# KeyPad.net
KiCad netlist of a schematic drawn in EAGLE
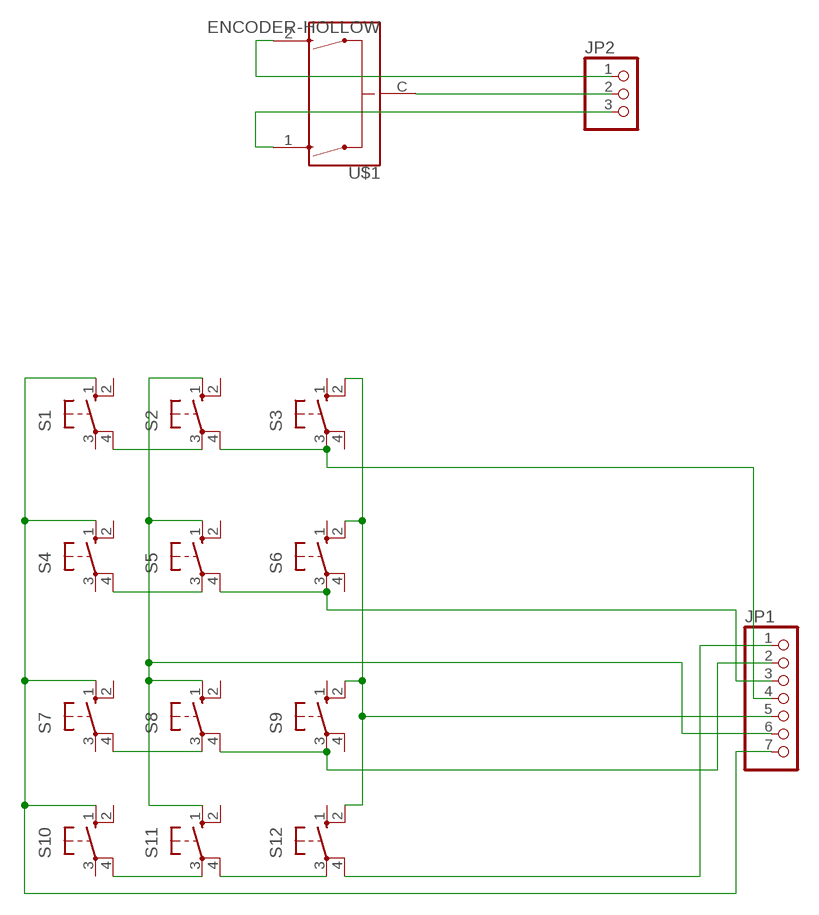
[diagram p0: schematic, sheet 1]

(export (version "E")
  (design (tool "Eeschema 10.0.6"))
  (components
    (comp (ref "JP1")
      (value "PINHD-1X7/90")
      (footprint "eagle-import:1X07_90")
      (libsource (lib "eagle-import") (part "PINHD-1X7/90"))
    )
    (comp (ref "JP2")
      (value "PINHD-1X3/90")
      (footprint "eagle-import:1X03_90")
      (libsource (lib "eagle-import") (part "PINHD-1X3/90"))
    )
    (comp (ref "S1")
      (value "40-XX")
      (footprint "eagle-import:B3F-40XX")
      (fields (field (name "MF") "OMRON COMPONENTS USA") (field (name "MPN") "B3F-4000"))
      (libsource (lib "eagle-import") (part "40-XX"))
    )
    (comp (ref "S2")
      (value "40-XX")
      (footprint "eagle-import:B3F-40XX")
      (fields (field (name "MF") "OMRON COMPONENTS USA") (field (name "MPN") "B3F-4000"))
      (libsource (lib "eagle-import") (part "40-XX"))
    )
    (comp (ref "S3")
      (value "40-XX")
      (footprint "eagle-import:B3F-40XX")
      (fields (field (name "MF") "OMRON COMPONENTS USA") (field (name "MPN") "B3F-4000"))
      (libsource (lib "eagle-import") (part "40-XX"))
    )
    (comp (ref "S4")
      (value "40-XX")
      (footprint "eagle-import:B3F-40XX")
      (fields (field (name "MF") "OMRON COMPONENTS USA") (field (name "MPN") "B3F-4000"))
      (libsource (lib "eagle-import") (part "40-XX"))
    )
    (comp (ref "S5")
      (value "40-XX")
      (footprint "eagle-import:B3F-40XX")
      (fields (field (name "MF") "OMRON COMPONENTS USA") (field (name "MPN") "B3F-4000"))
      (libsource (lib "eagle-import") (part "40-XX"))
    )
    (comp (ref "S6")
      (value "40-XX")
      (footprint "eagle-import:B3F-40XX")
      (fields (field (name "MF") "OMRON COMPONENTS USA") (field (name "MPN") "B3F-4000"))
      (libsource (lib "eagle-import") (part "40-XX"))
    )
    (comp (ref "S7")
      (value "40-XX")
      (footprint "eagle-import:B3F-40XX")
      (fields (field (name "MF") "OMRON COMPONENTS USA") (field (name "MPN") "B3F-4000"))
      (libsource (lib "eagle-import") (part "40-XX"))
    )
    (comp (ref "S8")
      (value "40-XX")
      (footprint "eagle-import:B3F-40XX")
      (fields (field (name "MF") "OMRON COMPONENTS USA") (field (name "MPN") "B3F-4000"))
      (libsource (lib "eagle-import") (part "40-XX"))
    )
    (comp (ref "S9")
      (value "40-XX")
      (footprint "eagle-import:B3F-40XX")
      (fields (field (name "MF") "OMRON COMPONENTS USA") (field (name "MPN") "B3F-4000"))
      (libsource (lib "eagle-import") (part "40-XX"))
    )
    (comp (ref "S10")
      (value "40-XX")
      (footprint "eagle-import:B3F-40XX")
      (fields (field (name "MF") "OMRON COMPONENTS USA") (field (name "MPN") "B3F-4000"))
      (libsource (lib "eagle-import") (part "40-XX"))
    )
    (comp (ref "S11")
      (value "40-XX")
      (footprint "eagle-import:B3F-40XX")
      (fields (field (name "MF") "OMRON COMPONENTS USA") (field (name "MPN") "B3F-4000"))
      (libsource (lib "eagle-import") (part "40-XX"))
    )
    (comp (ref "S12")
      (value "40-XX")
      (footprint "eagle-import:B3F-40XX")
      (fields (field (name "MF") "OMRON COMPONENTS USA") (field (name "MPN") "B3F-4000"))
      (libsource (lib "eagle-import") (part "40-XX"))
    )
    (comp (ref "U$1")
      (value "ENCODER-HOLLOW")
      (footprint "eagle-import:HOLLOW-ENCODER")
      (libsource (lib "eagle-import") (part "ENCODER-HOLLOW"))
    )
  )
  (nets
    (net (code "1") (name "Net-(JP2-Pad2)") (class "Default")
      (node (ref "JP2") (pin "2") (pinfunction "2_2") (pintype "passive"))
      (node (ref "U$1") (pin "C") (pinfunction "C_C") (pintype "bidirectional"))
    )
    (net (code "2") (name "Net-(S1-P1)") (class "Default")
      (node (ref "S1") (pin "4") (pinfunction "P1_4") (pintype "passive"))
      (node (ref "S2") (pin "3") (pinfunction "P_3") (pintype "passive"))
    )
    (net (code "3") (name "Net-(S1-S)") (class "Default")
      (node (ref "JP1") (pin "7") (pinfunction "7_7") (pintype "passive"))
      (node (ref "S1") (pin "1") (pinfunction "S_1") (pintype "passive"))
      (node (ref "S10") (pin "1") (pinfunction "S_1") (pintype "passive"))
      (node (ref "S4") (pin "1") (pinfunction "S_1") (pintype "passive"))
      (node (ref "S7") (pin "1") (pinfunction "S_1") (pintype "passive"))
    )
    (net (code "4") (name "Net-(S2-P1)") (class "Default")
      (node (ref "JP1") (pin "4") (pinfunction "4_4") (pintype "passive"))
      (node (ref "S2") (pin "4") (pinfunction "P1_4") (pintype "passive"))
      (node (ref "S3") (pin "3") (pinfunction "P_3") (pintype "passive"))
    )
    (net (code "5") (name "Net-(S4-P1)") (class "Default")
      (node (ref "S4") (pin "4") (pinfunction "P1_4") (pintype "passive"))
      (node (ref "S5") (pin "3") (pinfunction "P_3") (pintype "passive"))
    )
    (net (code "6") (name "Net-(S5-P1)") (class "Default")
      (node (ref "JP1") (pin "3") (pinfunction "3_3") (pintype "passive"))
      (node (ref "S5") (pin "4") (pinfunction "P1_4") (pintype "passive"))
      (node (ref "S6") (pin "3") (pinfunction "P_3") (pintype "passive"))
    )
    (net (code "7") (name "Net-(S7-P1)") (class "Default")
      (node (ref "S7") (pin "4") (pinfunction "P1_4") (pintype "passive"))
      (node (ref "S8") (pin "3") (pinfunction "P_3") (pintype "passive"))
    )
    (net (code "8") (name "Net-(S8-P1)") (class "Default")
      (node (ref "JP1") (pin "2") (pinfunction "2_2") (pintype "passive"))
      (node (ref "S8") (pin "4") (pinfunction "P1_4") (pintype "passive"))
      (node (ref "S9") (pin "3") (pinfunction "P_3") (pintype "passive"))
    )
    (net (code "9") (name "Net-(S10-P1)") (class "Default")
      (node (ref "S10") (pin "4") (pinfunction "P1_4") (pintype "passive"))
      (node (ref "S11") (pin "3") (pinfunction "P_3") (pintype "passive"))
    )
    (net (code "10") (name "Net-(S11-P1)") (class "Default")
      (node (ref "S11") (pin "4") (pinfunction "P1_4") (pintype "passive"))
      (node (ref "S12") (pin "3") (pinfunction "P_3") (pintype "passive"))
    )
    (net (code "11") (name "Net-(S11-S)") (class "Default")
      (node (ref "JP1") (pin "6") (pinfunction "6_6") (pintype "passive"))
      (node (ref "S11") (pin "1") (pinfunction "S_1") (pintype "passive"))
      (node (ref "S2") (pin "1") (pinfunction "S_1") (pintype "passive"))
      (node (ref "S5") (pin "1") (pinfunction "S_1") (pintype "passive"))
      (node (ref "S8") (pin "1") (pinfunction "S_1") (pintype "passive"))
    )
    (net (code "12") (name "Net-(S12-P1)") (class "Default")
      (node (ref "JP1") (pin "1") (pinfunction "1_1") (pintype "passive"))
      (node (ref "S12") (pin "4") (pinfunction "P1_4") (pintype "passive"))
    )
    (net (code "13") (name "Net-(S12-S1)") (class "Default")
      (node (ref "JP1") (pin "5") (pinfunction "5_5") (pintype "passive"))
      (node (ref "S12") (pin "2") (pinfunction "S1_2") (pintype "passive"))
      (node (ref "S3") (pin "2") (pinfunction "S1_2") (pintype "passive"))
      (node (ref "S6") (pin "2") (pinfunction "S1_2") (pintype "passive"))
      (node (ref "S9") (pin "2") (pinfunction "S1_2") (pintype "passive"))
    )
    (net (code "14") (name "Net-(U$1-A)") (class "Default")
      (node (ref "JP2") (pin "3") (pinfunction "3_3") (pintype "passive"))
      (node (ref "U$1") (pin "1") (pinfunction "A_1") (pintype "bidirectional"))
    )
    (net (code "15") (name "Net-(U$1-B)") (class "Default")
      (node (ref "JP2") (pin "1") (pinfunction "1_1") (pintype "passive"))
      (node (ref "U$1") (pin "2") (pinfunction "B_2") (pintype "bidirectional"))
    )
    (net (code "16") (name "unconnected-(S1-P-Pad3)") (class "Default")
      (node (ref "S1") (pin "3") (pinfunction "P_3") (pintype "passive"))
    )
    (net (code "17") (name "unconnected-(S1-S1-Pad2)") (class "Default")
      (node (ref "S1") (pin "2") (pinfunction "S1_2") (pintype "passive"))
    )
    (net (code "18") (name "unconnected-(S2-S1-Pad2)") (class "Default")
      (node (ref "S2") (pin "2") (pinfunction "S1_2") (pintype "passive"))
    )
    (net (code "19") (name "unconnected-(S3-P1-Pad4)") (class "Default")
      (node (ref "S3") (pin "4") (pinfunction "P1_4") (pintype "passive"))
    )
    (net (code "20") (name "unconnected-(S3-S-Pad1)") (class "Default")
      (node (ref "S3") (pin "1") (pinfunction "S_1") (pintype "passive"))
    )
    (net (code "21") (name "unconnected-(S4-P-Pad3)") (class "Default")
      (node (ref "S4") (pin "3") (pinfunction "P_3") (pintype "passive"))
    )
    (net (code "22") (name "unconnected-(S4-S1-Pad2)") (class "Default")
      (node (ref "S4") (pin "2") (pinfunction "S1_2") (pintype "passive"))
    )
    (net (code "23") (name "unconnected-(S5-S1-Pad2)") (class "Default")
      (node (ref "S5") (pin "2") (pinfunction "S1_2") (pintype "passive"))
    )
    (net (code "24") (name "unconnected-(S6-P1-Pad4)") (class "Default")
      (node (ref "S6") (pin "4") (pinfunction "P1_4") (pintype "passive"))
    )
    (net (code "25") (name "unconnected-(S6-S-Pad1)") (class "Default")
      (node (ref "S6") (pin "1") (pinfunction "S_1") (pintype "passive"))
    )
    (net (code "26") (name "unconnected-(S7-P-Pad3)") (class "Default")
      (node (ref "S7") (pin "3") (pinfunction "P_3") (pintype "passive"))
    )
    (net (code "27") (name "unconnected-(S7-S1-Pad2)") (class "Default")
      (node (ref "S7") (pin "2") (pinfunction "S1_2") (pintype "passive"))
    )
    (net (code "28") (name "unconnected-(S8-S1-Pad2)") (class "Default")
      (node (ref "S8") (pin "2") (pinfunction "S1_2") (pintype "passive"))
    )
    (net (code "29") (name "unconnected-(S9-P1-Pad4)") (class "Default")
      (node (ref "S9") (pin "4") (pinfunction "P1_4") (pintype "passive"))
    )
    (net (code "30") (name "unconnected-(S9-S-Pad1)") (class "Default")
      (node (ref "S9") (pin "1") (pinfunction "S_1") (pintype "passive"))
    )
    (net (code "31") (name "unconnected-(S10-P-Pad3)") (class "Default")
      (node (ref "S10") (pin "3") (pinfunction "P_3") (pintype "passive"))
    )
    (net (code "32") (name "unconnected-(S10-S1-Pad2)") (class "Default")
      (node (ref "S10") (pin "2") (pinfunction "S1_2") (pintype "passive"))
    )
    (net (code "33") (name "unconnected-(S11-S1-Pad2)") (class "Default")
      (node (ref "S11") (pin "2") (pinfunction "S1_2") (pintype "passive"))
    )
    (net (code "34") (name "unconnected-(S12-S-Pad1)") (class "Default")
      (node (ref "S12") (pin "1") (pinfunction "S_1") (pintype "passive"))
    )
  )
)
